# Szineszfeny_mego.net
KiCad netlist of a schematic drawn in EAGLE
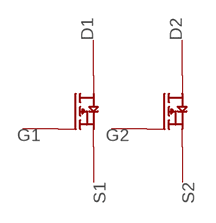
[diagram p0: schematic, sheet 1]

(export (version "E")
  (design (tool "Eeschema 10.0.6"))
  (components
    (comp (ref "D1")
      (value "PADSMD_KICSI")
      (footprint "eagle-import:PAD_SMD_KICSI")
      (libsource (lib "eagle-import") (part "PADSMD_KICSI"))
    )
    (comp (ref "D2")
      (value "PADSMD_KICSI")
      (footprint "eagle-import:PAD_SMD_KICSI")
      (libsource (lib "eagle-import") (part "PADSMD_KICSI"))
    )
    (comp (ref "G1")
      (value "PADSMD_KICSI")
      (footprint "eagle-import:PAD_SMD_KICSI")
      (libsource (lib "eagle-import") (part "PADSMD_KICSI"))
    )
    (comp (ref "G2")
      (value "PADSMD_KICSI")
      (footprint "eagle-import:PAD_SMD_KICSI")
      (libsource (lib "eagle-import") (part "PADSMD_KICSI"))
    )
    (comp (ref "S1")
      (value "PADSMD_KICSI")
      (footprint "eagle-import:PAD_SMD_KICSI")
      (libsource (lib "eagle-import") (part "PADSMD_KICSI"))
    )
    (comp (ref "S2")
      (value "PADSMD_KICSI")
      (footprint "eagle-import:PAD_SMD_KICSI")
      (libsource (lib "eagle-import") (part "PADSMD_KICSI"))
    )
    (comp (ref "U$1")
      (value "AP2625GY-HF-3SOT26")
      (footprint "eagle-import:SOT26")
      (libsource (lib "eagle-import") (part "AP2625GY-HF-3SOT26"))
    )
  )
  (nets
    (net (code "1") (name "Net-(D1-P$1)") (class "Default")
      (node (ref "D1") (pin "P$4") (pinfunction "P$1_P$4") (pintype "bidirectional"))
      (node (ref "U$1") (pin "P$6") (pinfunction "D_P$6") (pintype "passive"))
    )
    (net (code "2") (name "Net-(D2-P$1)") (class "Default")
      (node (ref "D2") (pin "P$4") (pinfunction "P$1_P$4") (pintype "bidirectional"))
      (node (ref "U$1") (pin "P$4") (pinfunction "D_P$4") (pintype "passive"))
    )
    (net (code "3") (name "Net-(G1-P$1)") (class "Default")
      (node (ref "G1") (pin "P$4") (pinfunction "P$1_P$4") (pintype "bidirectional"))
      (node (ref "U$1") (pin "P$1") (pinfunction "G_P$1") (pintype "passive"))
    )
    (net (code "4") (name "Net-(G2-P$1)") (class "Default")
      (node (ref "G2") (pin "P$4") (pinfunction "P$1_P$4") (pintype "bidirectional"))
      (node (ref "U$1") (pin "P$3") (pinfunction "G_P$3") (pintype "passive"))
    )
    (net (code "5") (name "Net-(S1-P$1)") (class "Default")
      (node (ref "S1") (pin "P$4") (pinfunction "P$1_P$4") (pintype "bidirectional"))
      (node (ref "U$1") (pin "P$5") (pinfunction "S_P$5") (pintype "passive"))
    )
    (net (code "6") (name "Net-(S2-P$1)") (class "Default")
      (node (ref "S2") (pin "P$4") (pinfunction "P$1_P$4") (pintype "bidirectional"))
      (node (ref "U$1") (pin "P$2") (pinfunction "S_P$2") (pintype "passive"))
    )
  )
)
